# 780-00012-P2_rev2_Sch_M2_Focus_Drive.net
KiCad netlist of a schematic drawn in Altium Designer
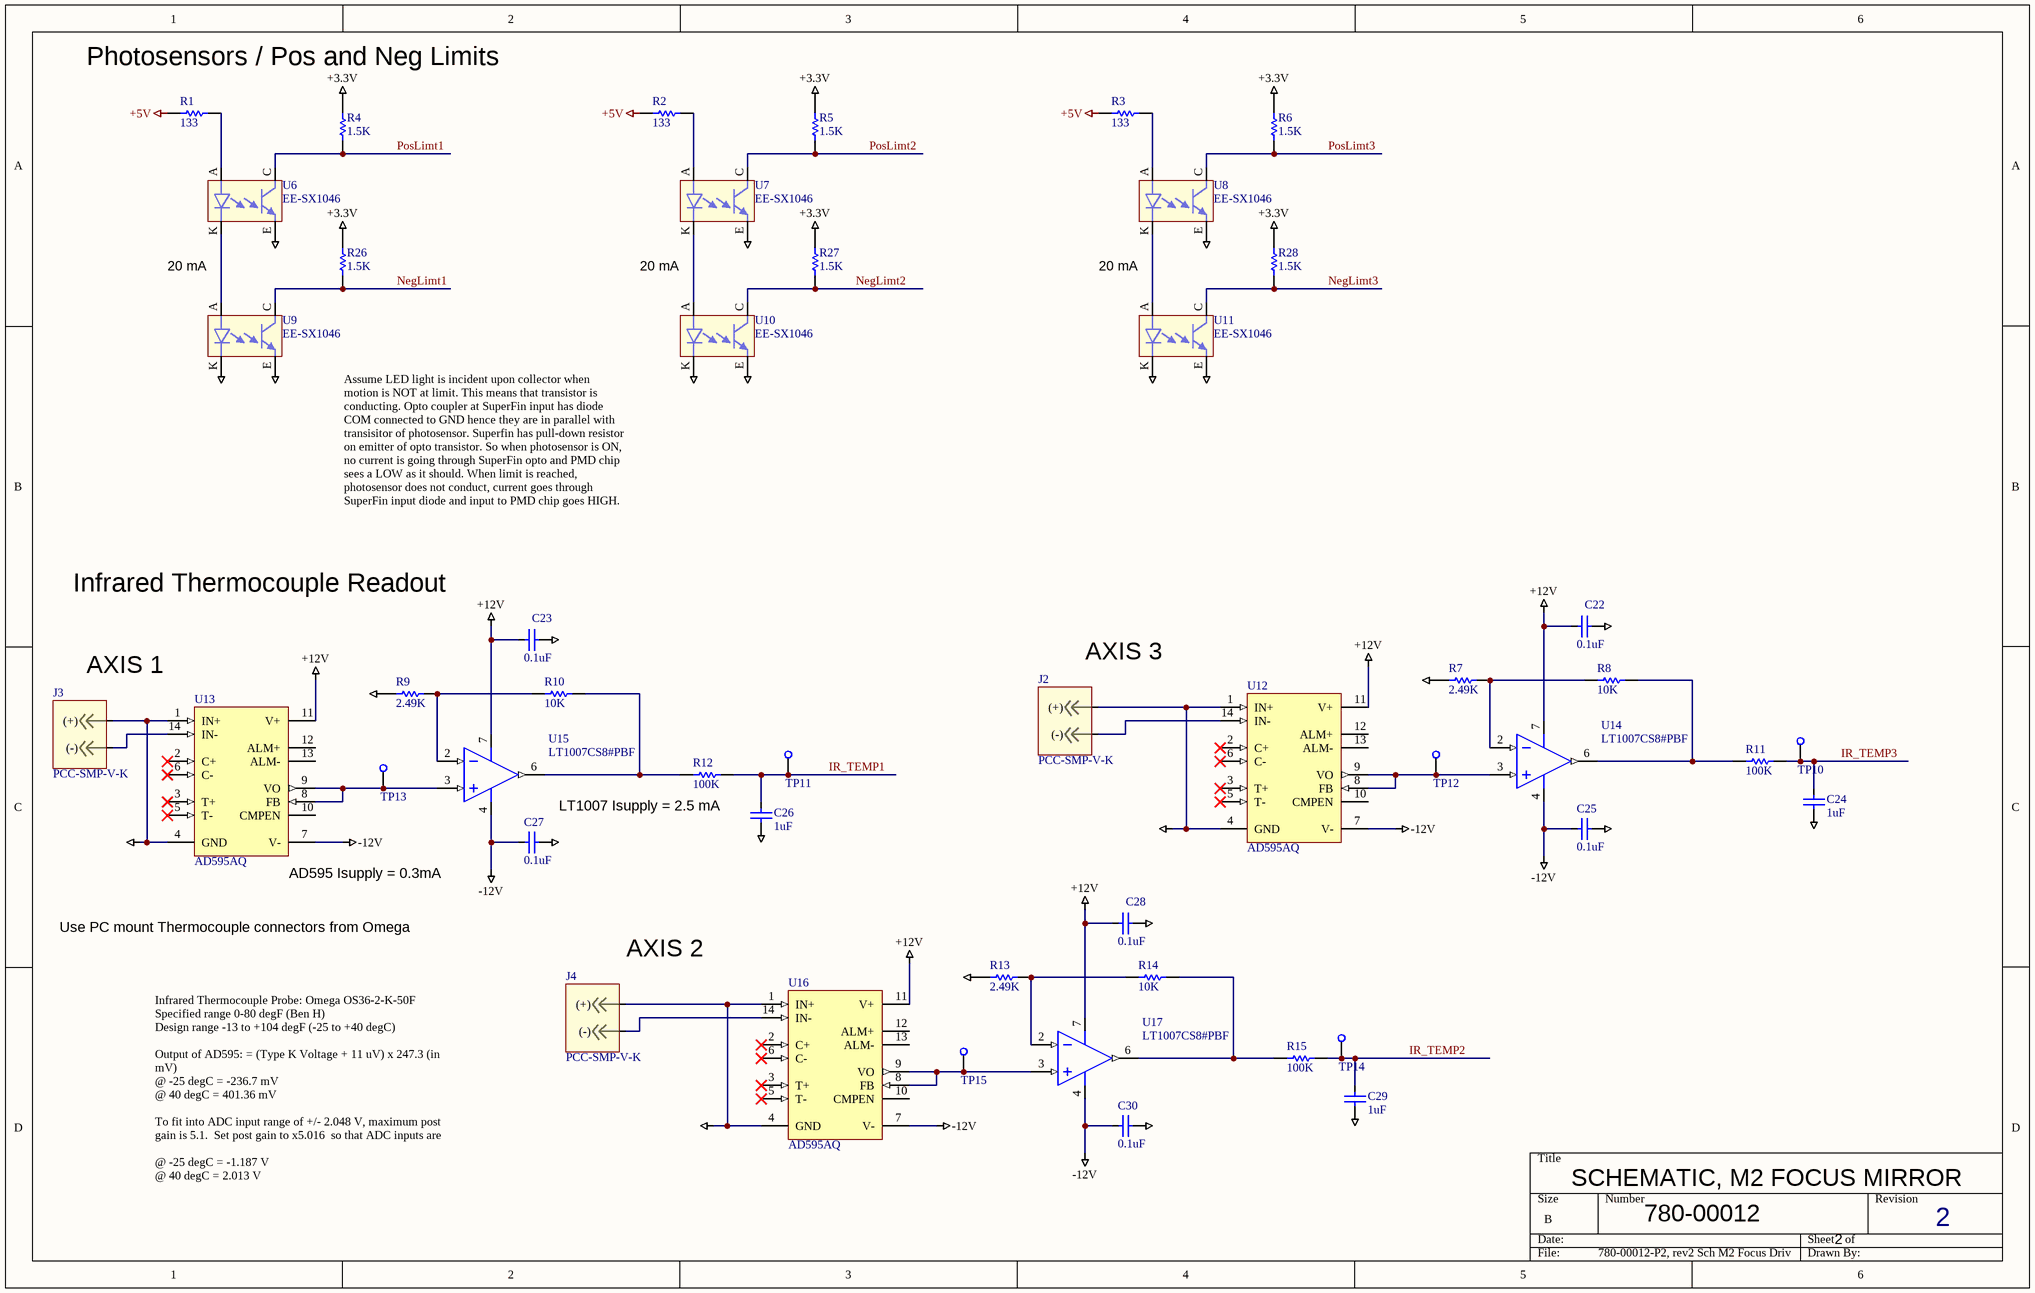
[diagram p0: 780-00012-P2, rev2 Sch M2 Focus Drive.SchDoc]

(export (version "E")
  (design (tool "Eeschema 10.0.6"))
  (components
    (comp (ref "C22")
      (value "0.1uF")
      (footprint "SMD_0805")
      (description "Capacitor")
      (fields (field (name "Comment") "Cap SMD"))
      (libsource (lib "Richs Schematic Components") (part "Cap SMD"))
    )
    (comp (ref "C23")
      (value "0.1uF")
      (footprint "SMD_0805")
      (description "Capacitor")
      (fields (field (name "Comment") "Cap SMD"))
      (libsource (lib "Richs Schematic Components") (part "Cap SMD"))
    )
    (comp (ref "C24")
      (value "1uF")
      (footprint "SMD_0805")
      (description "Capacitor")
      (fields (field (name "Comment") "Cap SMD"))
      (libsource (lib "Richs Schematic Components") (part "Cap SMD"))
    )
    (comp (ref "C25")
      (value "0.1uF")
      (footprint "SMD_0805")
      (description "Capacitor")
      (fields (field (name "Comment") "Cap SMD"))
      (libsource (lib "Richs Schematic Components") (part "Cap SMD"))
    )
    (comp (ref "C26")
      (value "1uF")
      (footprint "SMD_0805")
      (description "Capacitor")
      (fields (field (name "Comment") "Cap SMD"))
      (libsource (lib "Richs Schematic Components") (part "Cap SMD"))
    )
    (comp (ref "C27")
      (value "0.1uF")
      (footprint "SMD_0805")
      (description "Capacitor")
      (fields (field (name "Comment") "Cap SMD"))
      (libsource (lib "Richs Schematic Components") (part "Cap SMD"))
    )
    (comp (ref "C28")
      (value "0.1uF")
      (footprint "SMD_0805")
      (description "Capacitor")
      (fields (field (name "Comment") "Cap SMD"))
      (libsource (lib "Richs Schematic Components") (part "Cap SMD"))
    )
    (comp (ref "C29")
      (value "1uF")
      (footprint "SMD_0805")
      (description "Capacitor")
      (fields (field (name "Comment") "Cap SMD"))
      (libsource (lib "Richs Schematic Components") (part "Cap SMD"))
    )
    (comp (ref "C30")
      (value "0.1uF")
      (footprint "SMD_0805")
      (description "Capacitor")
      (fields (field (name "Comment") "Cap SMD"))
      (libsource (lib "Richs Schematic Components") (part "Cap SMD"))
    )
    (comp (ref "J2")
      (value "PCC-SMP-V-K")
      (footprint "THERMOCOUPLE")
      (description "T/C Conn PCB mount vertical")
      (libsource (lib "Richs Schematic Components") (part "Thermocouple Connector"))
    )
    (comp (ref "J3")
      (value "PCC-SMP-V-K")
      (footprint "THERMOCOUPLE")
      (description "T/C Conn PCB mount vertical")
      (libsource (lib "Richs Schematic Components") (part "Thermocouple Connector"))
    )
    (comp (ref "J4")
      (value "PCC-SMP-V-K")
      (footprint "THERMOCOUPLE")
      (description "T/C Conn PCB mount vertical")
      (libsource (lib "Richs Schematic Components") (part "Thermocouple Connector"))
    )
    (comp (ref "R1")
      (value "133")
      (footprint "SMD_0805")
      (description "Resistor 0805")
      (fields (field (name "MANUFACTURER") "Vishay/Dale") (field (name "Comment") "Res 0805"))
      (libsource (lib "Richs Schematic Components") (part "Res SMD"))
    )
    (comp (ref "R2")
      (value "133")
      (footprint "SMD_0805")
      (description "Resistor 0805")
      (fields (field (name "MANUFACTURER") "Vishay/Dale") (field (name "Comment") "Res 0805"))
      (libsource (lib "Richs Schematic Components") (part "Res SMD"))
    )
    (comp (ref "R3")
      (value "133")
      (footprint "SMD_0805")
      (description "Resistor 0805")
      (fields (field (name "MANUFACTURER") "Vishay/Dale") (field (name "Comment") "Res 0805"))
      (libsource (lib "Richs Schematic Components") (part "Res SMD"))
    )
    (comp (ref "R4")
      (value "1.5K")
      (footprint "SMD_0805")
      (description "Resistor 0805")
      (fields (field (name "MANUFACTURER") "Vishay/Dale") (field (name "Comment") "Res 0805"))
      (libsource (lib "Richs Schematic Components") (part "Res SMD"))
    )
    (comp (ref "R5")
      (value "1.5K")
      (footprint "SMD_0805")
      (description "Resistor 0805")
      (fields (field (name "MANUFACTURER") "Vishay/Dale") (field (name "Comment") "Res 0805"))
      (libsource (lib "Richs Schematic Components") (part "Res SMD"))
    )
    (comp (ref "R6")
      (value "1.5K")
      (footprint "SMD_0805")
      (description "Resistor 0805")
      (fields (field (name "MANUFACTURER") "Vishay/Dale") (field (name "Comment") "Res 0805"))
      (libsource (lib "Richs Schematic Components") (part "Res SMD"))
    )
    (comp (ref "R7")
      (value "2.49K")
      (footprint "SMD_0805")
      (description "Resistor 0805")
      (fields (field (name "MANUFACTURER") "Vishay/Dale") (field (name "Comment") "Res 0805"))
      (libsource (lib "Richs Schematic Components") (part "Res SMD"))
    )
    (comp (ref "R8")
      (value "10K")
      (footprint "SMD_0805")
      (description "Resistor 0805")
      (fields (field (name "MANUFACTURER") "Vishay/Dale") (field (name "Comment") "Res 0805"))
      (libsource (lib "Richs Schematic Components") (part "Res SMD"))
    )
    (comp (ref "R9")
      (value "2.49K")
      (footprint "SMD_0805")
      (description "Resistor 0805")
      (fields (field (name "MANUFACTURER") "Vishay/Dale") (field (name "Comment") "Res 0805"))
      (libsource (lib "Richs Schematic Components") (part "Res SMD"))
    )
    (comp (ref "R10")
      (value "10K")
      (footprint "SMD_0805")
      (description "Resistor 0805")
      (fields (field (name "MANUFACTURER") "Vishay/Dale") (field (name "Comment") "Res 0805"))
      (libsource (lib "Richs Schematic Components") (part "Res SMD"))
    )
    (comp (ref "R11")
      (value "100K")
      (footprint "SMD_0805")
      (description "Resistor 0805")
      (fields (field (name "MANUFACTURER") "Vishay/Dale") (field (name "Comment") "Res 0805"))
      (libsource (lib "Richs Schematic Components") (part "Res SMD"))
    )
    (comp (ref "R12")
      (value "100K")
      (footprint "SMD_0805")
      (description "Resistor 0805")
      (fields (field (name "MANUFACTURER") "Vishay/Dale") (field (name "Comment") "Res 0805"))
      (libsource (lib "Richs Schematic Components") (part "Res SMD"))
    )
    (comp (ref "R13")
      (value "2.49K")
      (footprint "SMD_0805")
      (description "Resistor 0805")
      (fields (field (name "MANUFACTURER") "Vishay/Dale") (field (name "Comment") "Res 0805"))
      (libsource (lib "Richs Schematic Components") (part "Res SMD"))
    )
    (comp (ref "R14")
      (value "10K")
      (footprint "SMD_0805")
      (description "Resistor 0805")
      (fields (field (name "MANUFACTURER") "Vishay/Dale") (field (name "Comment") "Res 0805"))
      (libsource (lib "Richs Schematic Components") (part "Res SMD"))
    )
    (comp (ref "R15")
      (value "100K")
      (footprint "SMD_0805")
      (description "Resistor 0805")
      (fields (field (name "MANUFACTURER") "Vishay/Dale") (field (name "Comment") "Res 0805"))
      (libsource (lib "Richs Schematic Components") (part "Res SMD"))
    )
    (comp (ref "R26")
      (value "1.5K")
      (footprint "SMD_0805")
      (description "Resistor 0805")
      (fields (field (name "MANUFACTURER") "Vishay/Dale") (field (name "Comment") "Res 0805"))
      (libsource (lib "Richs Schematic Components") (part "Res SMD"))
    )
    (comp (ref "R27")
      (value "1.5K")
      (footprint "SMD_0805")
      (description "Resistor 0805")
      (fields (field (name "MANUFACTURER") "Vishay/Dale") (field (name "Comment") "Res 0805"))
      (libsource (lib "Richs Schematic Components") (part "Res SMD"))
    )
    (comp (ref "R28")
      (value "1.5K")
      (footprint "SMD_0805")
      (description "Resistor 0805")
      (fields (field (name "MANUFACTURER") "Vishay/Dale") (field (name "Comment") "Res 0805"))
      (libsource (lib "Richs Schematic Components") (part "Res SMD"))
    )
    (comp (ref "TP10")
      (value "Test Point SMD")
      (footprint "SMD_TEST POINT")
      (description "SMD loop test point")
      (libsource (lib "Richs Schematic Components") (part "Test Point SMD"))
    )
    (comp (ref "TP11")
      (value "Test Point SMD")
      (footprint "SMD_TEST POINT")
      (description "SMD loop test point")
      (libsource (lib "Richs Schematic Components") (part "Test Point SMD"))
    )
    (comp (ref "TP12")
      (value "Test Point SMD")
      (footprint "SMD_TEST POINT")
      (description "SMD loop test point")
      (libsource (lib "Richs Schematic Components") (part "Test Point SMD"))
    )
    (comp (ref "TP13")
      (value "Test Point SMD")
      (footprint "SMD_TEST POINT")
      (description "SMD loop test point")
      (libsource (lib "Richs Schematic Components") (part "Test Point SMD"))
    )
    (comp (ref "TP14")
      (value "Test Point SMD")
      (footprint "SMD_TEST POINT")
      (description "SMD loop test point")
      (libsource (lib "Richs Schematic Components") (part "Test Point SMD"))
    )
    (comp (ref "TP15")
      (value "Test Point SMD")
      (footprint "SMD_TEST POINT")
      (description "SMD loop test point")
      (libsource (lib "Richs Schematic Components") (part "Test Point SMD"))
    )
    (comp (ref "U6")
      (value "EE-SX1046")
      (footprint "Photo-sensor")
      (description "Omron EE-SX1046")
      (libsource (lib "Richs Schematic Components") (part "Photo-sensor"))
    )
    (comp (ref "U7")
      (value "EE-SX1046")
      (footprint "Photo-sensor")
      (description "Omron EE-SX1046")
      (libsource (lib "Richs Schematic Components") (part "Photo-sensor"))
    )
    (comp (ref "U8")
      (value "EE-SX1046")
      (footprint "Photo-sensor")
      (description "Omron EE-SX1046")
      (libsource (lib "Richs Schematic Components") (part "Photo-sensor"))
    )
    (comp (ref "U9")
      (value "EE-SX1046")
      (footprint "Photo-sensor")
      (description "Omron EE-SX1046")
      (libsource (lib "Richs Schematic Components") (part "Photo-sensor"))
    )
    (comp (ref "U10")
      (value "EE-SX1046")
      (footprint "Photo-sensor")
      (description "Omron EE-SX1046")
      (libsource (lib "Richs Schematic Components") (part "Photo-sensor"))
    )
    (comp (ref "U11")
      (value "EE-SX1046")
      (footprint "Photo-sensor")
      (description "Omron EE-SX1046")
      (libsource (lib "Richs Schematic Components") (part "Photo-sensor"))
    )
    (comp (ref "U12")
      (value "AD595AQ")
      (footprint "Q-14_A")
      (description "Monolithic Thermocouple Amplifier with Cold Junction Compensation")
      (fields (field (name "MANUFACTURER") "Analog Devices"))
      (libsource (lib "AD Thermocouple Amplifier") (part "AD595AQ"))
    )
    (comp (ref "U13")
      (value "AD595AQ")
      (footprint "Q-14_A")
      (description "Monolithic Thermocouple Amplifier with Cold Junction Compensation")
      (fields (field (name "MANUFACTURER") "Analog Devices"))
      (libsource (lib "AD Thermocouple Amplifier") (part "AD595AQ"))
    )
    (comp (ref "U14")
      (value "LT1007CS8#PBF")
      (footprint "S8_M")
      (description "Low Noise BJT input opamp")
      (fields (field (name "MANUFACTURER") "Linear Tech"))
      (libsource (lib "Richs Schematic Components") (part "LT1007CS8#PBF"))
    )
    (comp (ref "U15")
      (value "LT1007CS8#PBF")
      (footprint "S8_M")
      (description "Low Noise BJT input opamp")
      (fields (field (name "MANUFACTURER") "Linear Tech"))
      (libsource (lib "Richs Schematic Components") (part "LT1007CS8#PBF"))
    )
    (comp (ref "U16")
      (value "AD595AQ")
      (footprint "Q-14_A")
      (description "Monolithic Thermocouple Amplifier with Cold Junction Compensation")
      (fields (field (name "MANUFACTURER") "Analog Devices"))
      (libsource (lib "AD Thermocouple Amplifier") (part "AD595AQ"))
    )
    (comp (ref "U17")
      (value "LT1007CS8#PBF")
      (footprint "S8_M")
      (description "Low Noise BJT input opamp")
      (fields (field (name "MANUFACTURER") "Linear Tech"))
      (libsource (lib "Richs Schematic Components") (part "LT1007CS8#PBF"))
    )
  )
  (nets
    (net (code "1") (name "+3.3V") (class "Default")
      (node (ref "R26") (pin "2") (pinfunction "2_2") (pintype "passive"))
      (node (ref "R27") (pin "2") (pinfunction "2_2") (pintype "passive"))
      (node (ref "R28") (pin "2") (pinfunction "2_2") (pintype "passive"))
      (node (ref "R4") (pin "2") (pinfunction "2_2") (pintype "passive"))
      (node (ref "R5") (pin "2") (pinfunction "2_2") (pintype "passive"))
      (node (ref "R6") (pin "2") (pinfunction "2_2") (pintype "passive"))
    )
    (net (code "2") (name "+5V") (class "Default")
      (node (ref "R1") (pin "2") (pinfunction "2_2") (pintype "passive"))
      (node (ref "R2") (pin "2") (pinfunction "2_2") (pintype "passive"))
      (node (ref "R3") (pin "2") (pinfunction "2_2") (pintype "passive"))
    )
    (net (code "3") (name "+12V") (class "Default")
      (node (ref "C22") (pin "2") (pinfunction "2_2") (pintype "passive"))
      (node (ref "C23") (pin "2") (pinfunction "2_2") (pintype "passive"))
      (node (ref "C28") (pin "2") (pinfunction "2_2") (pintype "passive"))
      (node (ref "U12") (pin "11") (pinfunction "V+_11") (pintype "power_in"))
      (node (ref "U13") (pin "11") (pinfunction "V+_11") (pintype "power_in"))
      (node (ref "U14") (pin "7") (pinfunction "V+_7") (pintype "power_in"))
      (node (ref "U15") (pin "7") (pinfunction "V+_7") (pintype "power_in"))
      (node (ref "U16") (pin "11") (pinfunction "V+_11") (pintype "power_in"))
      (node (ref "U17") (pin "7") (pinfunction "V+_7") (pintype "power_in"))
    )
    (net (code "4") (name "-12V") (class "Default")
      (node (ref "C25") (pin "2") (pinfunction "2_2") (pintype "passive"))
      (node (ref "C27") (pin "2") (pinfunction "2_2") (pintype "passive"))
      (node (ref "C30") (pin "2") (pinfunction "2_2") (pintype "passive"))
      (node (ref "U12") (pin "7") (pinfunction "V-_7") (pintype "power_in"))
      (node (ref "U13") (pin "7") (pinfunction "V-_7") (pintype "power_in"))
      (node (ref "U14") (pin "4") (pinfunction "V-_4") (pintype "power_in"))
      (node (ref "U15") (pin "4") (pinfunction "V-_4") (pintype "power_in"))
      (node (ref "U16") (pin "7") (pinfunction "V-_7") (pintype "power_in"))
      (node (ref "U17") (pin "4") (pinfunction "V-_4") (pintype "power_in"))
    )
    (net (code "5") (name "/IR_TEMP1") (class "Default")
      (node (ref "C26") (pin "2") (pinfunction "2_2") (pintype "passive"))
      (node (ref "R12") (pin "2") (pinfunction "2_2") (pintype "passive"))
      (node (ref "TP11") (pin "1") (pinfunction "TP_1") (pintype "passive"))
    )
    (net (code "6") (name "/IR_TEMP2") (class "Default")
      (node (ref "C29") (pin "2") (pinfunction "2_2") (pintype "passive"))
      (node (ref "R15") (pin "2") (pinfunction "2_2") (pintype "passive"))
      (node (ref "TP14") (pin "1") (pinfunction "TP_1") (pintype "passive"))
    )
    (net (code "7") (name "/IR_TEMP3") (class "Default")
      (node (ref "C24") (pin "2") (pinfunction "2_2") (pintype "passive"))
      (node (ref "R11") (pin "2") (pinfunction "2_2") (pintype "passive"))
      (node (ref "TP10") (pin "1") (pinfunction "TP_1") (pintype "passive"))
    )
    (net (code "8") (name "/NegLimt1") (class "Default")
      (node (ref "R26") (pin "1") (pinfunction "1_1") (pintype "passive"))
      (node (ref "U9") (pin "C") (pinfunction "collector_C") (pintype "passive"))
    )
    (net (code "9") (name "/NegLimt2") (class "Default")
      (node (ref "R27") (pin "1") (pinfunction "1_1") (pintype "passive"))
      (node (ref "U10") (pin "C") (pinfunction "collector_C") (pintype "passive"))
    )
    (net (code "10") (name "/NegLimt3") (class "Default")
      (node (ref "R28") (pin "1") (pinfunction "1_1") (pintype "passive"))
      (node (ref "U11") (pin "C") (pinfunction "collector_C") (pintype "passive"))
    )
    (net (code "11") (name "/PosLimt1") (class "Default")
      (node (ref "R4") (pin "1") (pinfunction "1_1") (pintype "passive"))
      (node (ref "U6") (pin "C") (pinfunction "collector_C") (pintype "passive"))
    )
    (net (code "12") (name "/PosLimt2") (class "Default")
      (node (ref "R5") (pin "1") (pinfunction "1_1") (pintype "passive"))
      (node (ref "U7") (pin "C") (pinfunction "collector_C") (pintype "passive"))
    )
    (net (code "13") (name "/PosLimt3") (class "Default")
      (node (ref "R6") (pin "1") (pinfunction "1_1") (pintype "passive"))
      (node (ref "U8") (pin "C") (pinfunction "collector_C") (pintype "passive"))
    )
    (net (code "14") (name "GND") (class "Default")
      (node (ref "C22") (pin "1") (pinfunction "1_1") (pintype "passive"))
      (node (ref "C23") (pin "1") (pinfunction "1_1") (pintype "passive"))
      (node (ref "C24") (pin "1") (pinfunction "1_1") (pintype "passive"))
      (node (ref "C25") (pin "1") (pinfunction "1_1") (pintype "passive"))
      (node (ref "C26") (pin "1") (pinfunction "1_1") (pintype "passive"))
      (node (ref "C27") (pin "1") (pinfunction "1_1") (pintype "passive"))
      (node (ref "C28") (pin "1") (pinfunction "1_1") (pintype "passive"))
      (node (ref "C29") (pin "1") (pinfunction "1_1") (pintype "passive"))
      (node (ref "C30") (pin "1") (pinfunction "1_1") (pintype "passive"))
      (node (ref "J2") (pin "1") (pinfunction "(+)_1") (pintype "passive"))
      (node (ref "J3") (pin "1") (pinfunction "(+)_1") (pintype "passive"))
      (node (ref "J4") (pin "1") (pinfunction "(+)_1") (pintype "passive"))
      (node (ref "R13") (pin "1") (pinfunction "1_1") (pintype "passive"))
      (node (ref "R7") (pin "1") (pinfunction "1_1") (pintype "passive"))
      (node (ref "R9") (pin "1") (pinfunction "1_1") (pintype "passive"))
      (node (ref "U10") (pin "E") (pinfunction "emitter_E") (pintype "passive"))
      (node (ref "U10") (pin "K") (pinfunction "cathode_K") (pintype "passive"))
      (node (ref "U11") (pin "E") (pinfunction "emitter_E") (pintype "passive"))
      (node (ref "U11") (pin "K") (pinfunction "cathode_K") (pintype "passive"))
      (node (ref "U12") (pin "1") (pinfunction "IN+_1") (pintype "input"))
      (node (ref "U12") (pin "4") (pinfunction "GND_4") (pintype "power_in"))
      (node (ref "U13") (pin "1") (pinfunction "IN+_1") (pintype "input"))
      (node (ref "U13") (pin "4") (pinfunction "GND_4") (pintype "power_in"))
      (node (ref "U16") (pin "1") (pinfunction "IN+_1") (pintype "input"))
      (node (ref "U16") (pin "4") (pinfunction "GND_4") (pintype "power_in"))
      (node (ref "U6") (pin "E") (pinfunction "emitter_E") (pintype "passive"))
      (node (ref "U7") (pin "E") (pinfunction "emitter_E") (pintype "passive"))
      (node (ref "U8") (pin "E") (pinfunction "emitter_E") (pintype "passive"))
      (node (ref "U9") (pin "E") (pinfunction "emitter_E") (pintype "passive"))
      (node (ref "U9") (pin "K") (pinfunction "cathode_K") (pintype "passive"))
    )
    (net (code "15") (name "Net-(J2-(-))") (class "Default")
      (node (ref "J2") (pin "2") (pinfunction "(-)_2") (pintype "passive"))
      (node (ref "U12") (pin "14") (pinfunction "IN-_14") (pintype "input"))
    )
    (net (code "16") (name "Net-(J3-(-))") (class "Default")
      (node (ref "J3") (pin "2") (pinfunction "(-)_2") (pintype "passive"))
      (node (ref "U13") (pin "14") (pinfunction "IN-_14") (pintype "input"))
    )
    (net (code "17") (name "Net-(J4-(-))") (class "Default")
      (node (ref "J4") (pin "2") (pinfunction "(-)_2") (pintype "passive"))
      (node (ref "U16") (pin "14") (pinfunction "IN-_14") (pintype "input"))
    )
    (net (code "18") (name "Net-(TP12-TP)") (class "Default")
      (node (ref "TP12") (pin "1") (pinfunction "TP_1") (pintype "passive"))
      (node (ref "U12") (pin "8") (pinfunction "FB_8") (pintype "input"))
      (node (ref "U12") (pin "9") (pinfunction "VO_9") (pintype "output"))
      (node (ref "U14") (pin "3") (pinfunction "IN+_3") (pintype "input"))
    )
    (net (code "19") (name "Net-(TP13-TP)") (class "Default")
      (node (ref "TP13") (pin "1") (pinfunction "TP_1") (pintype "passive"))
      (node (ref "U13") (pin "8") (pinfunction "FB_8") (pintype "input"))
      (node (ref "U13") (pin "9") (pinfunction "VO_9") (pintype "output"))
      (node (ref "U15") (pin "3") (pinfunction "IN+_3") (pintype "input"))
    )
    (net (code "20") (name "Net-(TP15-TP)") (class "Default")
      (node (ref "TP15") (pin "1") (pinfunction "TP_1") (pintype "passive"))
      (node (ref "U16") (pin "8") (pinfunction "FB_8") (pintype "input"))
      (node (ref "U16") (pin "9") (pinfunction "VO_9") (pintype "output"))
      (node (ref "U17") (pin "3") (pinfunction "IN+_3") (pintype "input"))
    )
    (net (code "21") (name "Net-(U6-anode)") (class "Default")
      (node (ref "R1") (pin "1") (pinfunction "1_1") (pintype "passive"))
      (node (ref "U6") (pin "A") (pinfunction "anode_A") (pintype "passive"))
    )
    (net (code "22") (name "Net-(U6-cathode)") (class "Default")
      (node (ref "U6") (pin "K") (pinfunction "cathode_K") (pintype "passive"))
      (node (ref "U9") (pin "A") (pinfunction "anode_A") (pintype "passive"))
    )
    (net (code "23") (name "Net-(U7-anode)") (class "Default")
      (node (ref "R2") (pin "1") (pinfunction "1_1") (pintype "passive"))
      (node (ref "U7") (pin "A") (pinfunction "anode_A") (pintype "passive"))
    )
    (net (code "24") (name "Net-(U8-anode)") (class "Default")
      (node (ref "R3") (pin "1") (pinfunction "1_1") (pintype "passive"))
      (node (ref "U8") (pin "A") (pinfunction "anode_A") (pintype "passive"))
    )
    (net (code "25") (name "Net-(U10-anode)") (class "Default")
      (node (ref "U10") (pin "A") (pinfunction "anode_A") (pintype "passive"))
      (node (ref "U7") (pin "K") (pinfunction "cathode_K") (pintype "passive"))
    )
    (net (code "26") (name "Net-(U11-anode)") (class "Default")
      (node (ref "U11") (pin "A") (pinfunction "anode_A") (pintype "passive"))
      (node (ref "U8") (pin "K") (pinfunction "cathode_K") (pintype "passive"))
    )
    (net (code "27") (name "Net-(U14-IN-)") (class "Default")
      (node (ref "R7") (pin "2") (pinfunction "2_2") (pintype "passive"))
      (node (ref "R8") (pin "1") (pinfunction "1_1") (pintype "passive"))
      (node (ref "U14") (pin "2") (pinfunction "IN-_2") (pintype "input"))
    )
    (net (code "28") (name "Net-(U14-OUT)") (class "Default")
      (node (ref "R11") (pin "1") (pinfunction "1_1") (pintype "passive"))
      (node (ref "R8") (pin "2") (pinfunction "2_2") (pintype "passive"))
      (node (ref "U14") (pin "6") (pinfunction "OUT_6") (pintype "output"))
    )
    (net (code "29") (name "Net-(U15-IN-)") (class "Default")
      (node (ref "R10") (pin "1") (pinfunction "1_1") (pintype "passive"))
      (node (ref "R9") (pin "2") (pinfunction "2_2") (pintype "passive"))
      (node (ref "U15") (pin "2") (pinfunction "IN-_2") (pintype "input"))
    )
    (net (code "30") (name "Net-(U15-OUT)") (class "Default")
      (node (ref "R10") (pin "2") (pinfunction "2_2") (pintype "passive"))
      (node (ref "R12") (pin "1") (pinfunction "1_1") (pintype "passive"))
      (node (ref "U15") (pin "6") (pinfunction "OUT_6") (pintype "output"))
    )
    (net (code "31") (name "Net-(U17-IN-)") (class "Default")
      (node (ref "R13") (pin "2") (pinfunction "2_2") (pintype "passive"))
      (node (ref "R14") (pin "1") (pinfunction "1_1") (pintype "passive"))
      (node (ref "U17") (pin "2") (pinfunction "IN-_2") (pintype "input"))
    )
    (net (code "32") (name "Net-(U17-OUT)") (class "Default")
      (node (ref "R14") (pin "2") (pinfunction "2_2") (pintype "passive"))
      (node (ref "R15") (pin "1") (pinfunction "1_1") (pintype "passive"))
      (node (ref "U17") (pin "6") (pinfunction "OUT_6") (pintype "output"))
    )
    (net (code "33") (name "unconnected-(U12-ALM+-Pad12)") (class "Default")
      (node (ref "U12") (pin "12") (pinfunction "ALM+_12") (pintype "passive"))
    )
    (net (code "34") (name "unconnected-(U12-ALM--Pad13)") (class "Default")
      (node (ref "U12") (pin "13") (pinfunction "ALM-_13") (pintype "passive"))
    )
    (net (code "35") (name "unconnected-(U12-C+-Pad2)") (class "Default")
      (node (ref "U12") (pin "2") (pinfunction "C+_2") (pintype "input+no_connect"))
    )
    (net (code "36") (name "unconnected-(U12-C--Pad6)") (class "Default")
      (node (ref "U12") (pin "6") (pinfunction "C-_6") (pintype "input+no_connect"))
    )
    (net (code "37") (name "unconnected-(U12-CMPEN-Pad10)") (class "Default")
      (node (ref "U12") (pin "10") (pinfunction "CMPEN_10") (pintype "passive"))
    )
    (net (code "38") (name "unconnected-(U12-T+-Pad3)") (class "Default")
      (node (ref "U12") (pin "3") (pinfunction "T+_3") (pintype "input+no_connect"))
    )
    (net (code "39") (name "unconnected-(U12-T--Pad5)") (class "Default")
      (node (ref "U12") (pin "5") (pinfunction "T-_5") (pintype "input+no_connect"))
    )
    (net (code "40") (name "unconnected-(U13-ALM+-Pad12)") (class "Default")
      (node (ref "U13") (pin "12") (pinfunction "ALM+_12") (pintype "passive"))
    )
    (net (code "41") (name "unconnected-(U13-ALM--Pad13)") (class "Default")
      (node (ref "U13") (pin "13") (pinfunction "ALM-_13") (pintype "passive"))
    )
    (net (code "42") (name "unconnected-(U13-C+-Pad2)") (class "Default")
      (node (ref "U13") (pin "2") (pinfunction "C+_2") (pintype "input+no_connect"))
    )
    (net (code "43") (name "unconnected-(U13-C--Pad6)") (class "Default")
      (node (ref "U13") (pin "6") (pinfunction "C-_6") (pintype "input+no_connect"))
    )
    (net (code "44") (name "unconnected-(U13-CMPEN-Pad10)") (class "Default")
      (node (ref "U13") (pin "10") (pinfunction "CMPEN_10") (pintype "passive"))
    )
    (net (code "45") (name "unconnected-(U13-T+-Pad3)") (class "Default")
      (node (ref "U13") (pin "3") (pinfunction "T+_3") (pintype "input+no_connect"))
    )
    (net (code "46") (name "unconnected-(U13-T--Pad5)") (class "Default")
      (node (ref "U13") (pin "5") (pinfunction "T-_5") (pintype "input+no_connect"))
    )
    (net (code "47") (name "unconnected-(U14-NC-Pad5)") (class "Default")
      (node (ref "U14") (pin "5") (pinfunction "NC_5") (pintype "passive"))
    )
    (net (code "48") (name "unconnected-(U14-VOSTRIM-Pad1)") (class "Default")
      (node (ref "U14") (pin "1") (pinfunction "VOSTRIM_1") (pintype "passive"))
    )
    (net (code "49") (name "unconnected-(U14-VOSTRIM-Pad8)") (class "Default")
      (node (ref "U14") (pin "8") (pinfunction "VOSTRIM_8") (pintype "passive"))
    )
    (net (code "50") (name "unconnected-(U15-NC-Pad5)") (class "Default")
      (node (ref "U15") (pin "5") (pinfunction "NC_5") (pintype "passive"))
    )
    (net (code "51") (name "unconnected-(U15-VOSTRIM-Pad1)") (class "Default")
      (node (ref "U15") (pin "1") (pinfunction "VOSTRIM_1") (pintype "passive"))
    )
    (net (code "52") (name "unconnected-(U15-VOSTRIM-Pad8)") (class "Default")
      (node (ref "U15") (pin "8") (pinfunction "VOSTRIM_8") (pintype "passive"))
    )
    (net (code "53") (name "unconnected-(U16-ALM+-Pad12)") (class "Default")
      (node (ref "U16") (pin "12") (pinfunction "ALM+_12") (pintype "passive"))
    )
    (net (code "54") (name "unconnected-(U16-ALM--Pad13)") (class "Default")
      (node (ref "U16") (pin "13") (pinfunction "ALM-_13") (pintype "passive"))
    )
    (net (code "55") (name "unconnected-(U16-C+-Pad2)") (class "Default")
      (node (ref "U16") (pin "2") (pinfunction "C+_2") (pintype "input+no_connect"))
    )
    (net (code "56") (name "unconnected-(U16-C--Pad6)") (class "Default")
      (node (ref "U16") (pin "6") (pinfunction "C-_6") (pintype "input+no_connect"))
    )
    (net (code "57") (name "unconnected-(U16-CMPEN-Pad10)") (class "Default")
      (node (ref "U16") (pin "10") (pinfunction "CMPEN_10") (pintype "passive"))
    )
    (net (code "58") (name "unconnected-(U16-T+-Pad3)") (class "Default")
      (node (ref "U16") (pin "3") (pinfunction "T+_3") (pintype "input+no_connect"))
    )
    (net (code "59") (name "unconnected-(U16-T--Pad5)") (class "Default")
      (node (ref "U16") (pin "5") (pinfunction "T-_5") (pintype "input+no_connect"))
    )
    (net (code "60") (name "unconnected-(U17-NC-Pad5)") (class "Default")
      (node (ref "U17") (pin "5") (pinfunction "NC_5") (pintype "passive"))
    )
    (net (code "61") (name "unconnected-(U17-VOSTRIM-Pad1)") (class "Default")
      (node (ref "U17") (pin "1") (pinfunction "VOSTRIM_1") (pintype "passive"))
    )
    (net (code "62") (name "unconnected-(U17-VOSTRIM-Pad8)") (class "Default")
      (node (ref "U17") (pin "8") (pinfunction "VOSTRIM_8") (pintype "passive"))
    )
  )
)
